# FPC_15ICS_80LEDS_150MM.net
KiCad netlist of a schematic drawn in Altium Designer
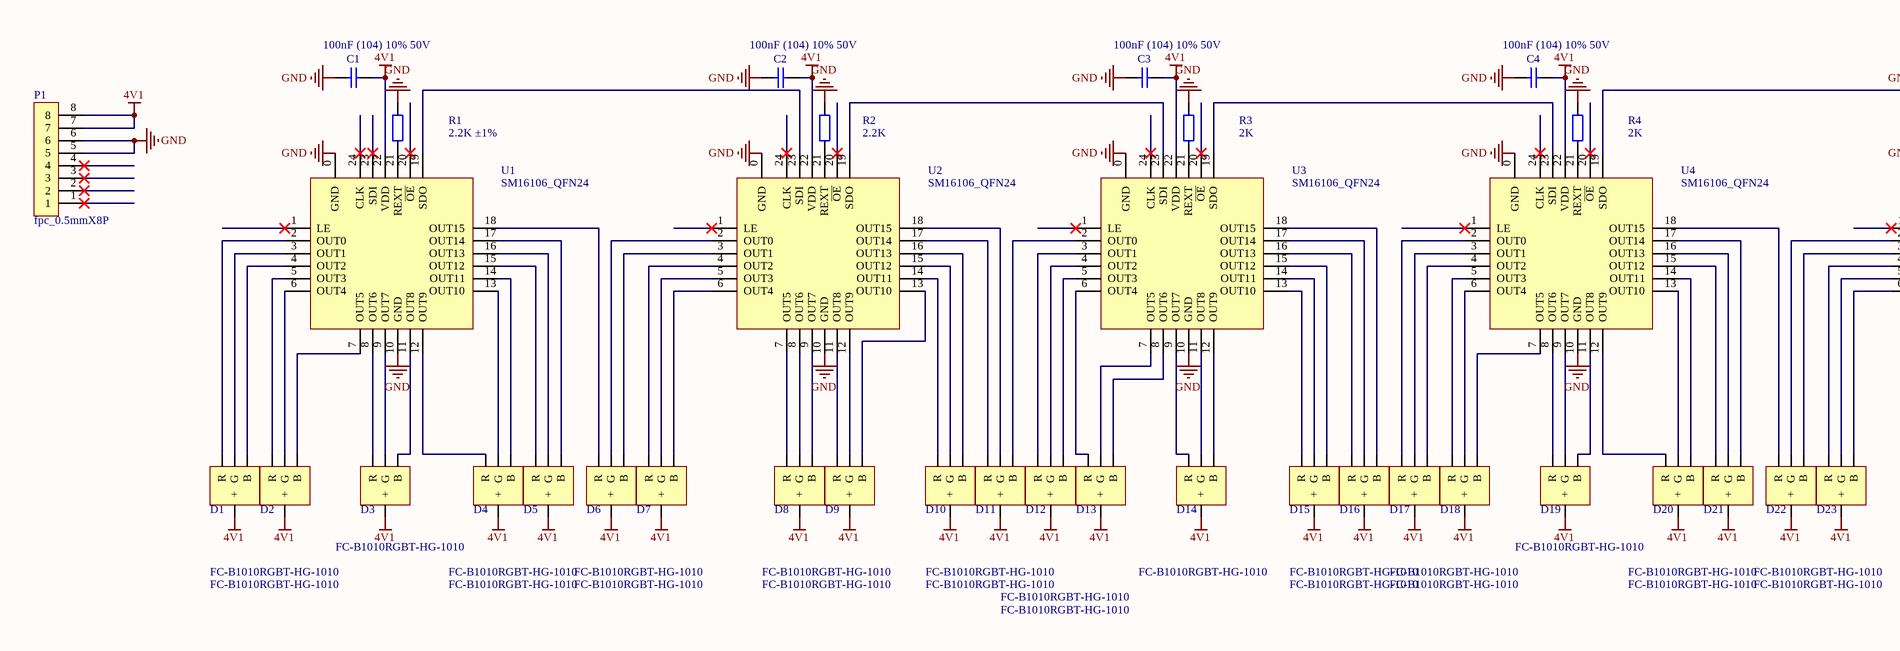
[diagram p0: FPC_15ICS_80LEDS_150MM.SchDoc, left]
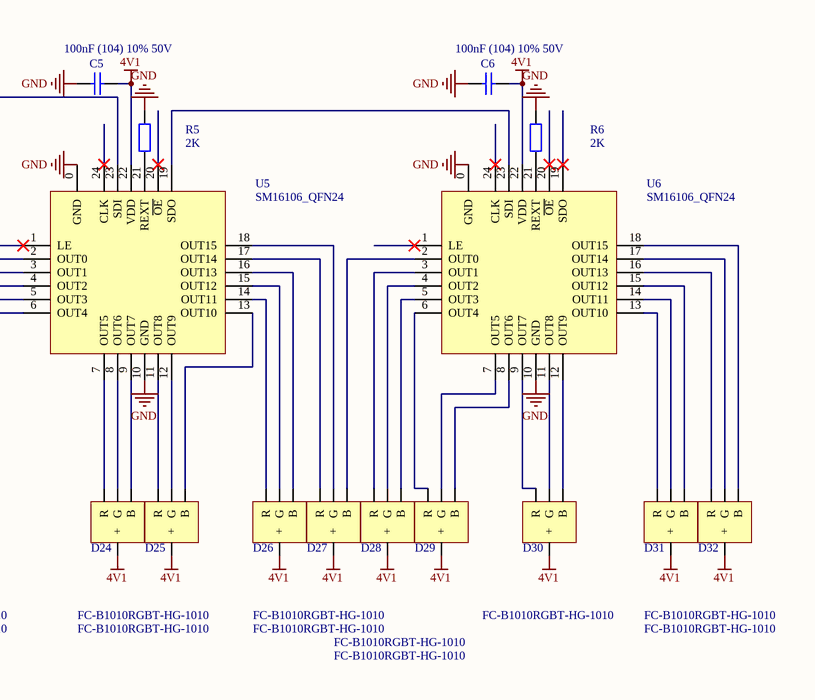
[diagram p1: FPC_15ICS_80LEDS_150MM.SchDoc, right]

(export (version "E")
  (design (tool "Eeschema 10.0.6"))
  (components
    (comp (ref "C1")
      (value "100nF (104) 10% 50V")
      (footprint "0402_C")
      (description "贴片电容")
      (libsource (lib "Cap") (part "0603 100nF (104) 10% 50V"))
    )
    (comp (ref "C2")
      (value "100nF (104) 10% 50V")
      (footprint "0402_C")
      (description "贴片电容")
      (libsource (lib "Cap") (part "0603 100nF (104) 10% 50V"))
    )
    (comp (ref "C3")
      (value "100nF (104) 10% 50V")
      (footprint "0402_C")
      (description "贴片电容")
      (libsource (lib "Cap") (part "0603 100nF (104) 10% 50V"))
    )
    (comp (ref "C4")
      (value "100nF (104) 10% 50V")
      (footprint "0402_C")
      (description "贴片电容")
      (libsource (lib "Cap") (part "0603 100nF (104) 10% 50V"))
    )
    (comp (ref "C5")
      (value "100nF (104) 10% 50V")
      (footprint "0402_C")
      (description "贴片电容")
      (libsource (lib "Cap") (part "0603 100nF (104) 10% 50V"))
    )
    (comp (ref "C6")
      (value "100nF (104) 10% 50V")
      (footprint "0402_C")
      (description "贴片电容")
      (libsource (lib "Cap") (part "0603 100nF (104) 10% 50V"))
    )
    (comp (ref "D1")
      (value "FC-B1010RGBT-HG-1010")
      (footprint "LED-SMD-0.385X0.45X0.45")
      (libsource (lib "TCPLib") (part "LED_RGB_1010"))
    )
    (comp (ref "D2")
      (value "FC-B1010RGBT-HG-1010")
      (footprint "LED-SMD-0.385X0.45X0.45")
      (libsource (lib "TCPLib") (part "LED_RGB_1010"))
    )
    (comp (ref "D3")
      (value "FC-B1010RGBT-HG-1010")
      (footprint "LED-SMD-0.385X0.45X0.45")
      (libsource (lib "TCPLib") (part "LED_RGB_1010"))
    )
    (comp (ref "D4")
      (value "FC-B1010RGBT-HG-1010")
      (footprint "LED-SMD-0.385X0.45X0.45")
      (libsource (lib "TCPLib") (part "LED_RGB_1010"))
    )
    (comp (ref "D5")
      (value "FC-B1010RGBT-HG-1010")
      (footprint "LED-SMD-0.385X0.45X0.45")
      (libsource (lib "TCPLib") (part "LED_RGB_1010"))
    )
    (comp (ref "D6")
      (value "FC-B1010RGBT-HG-1010")
      (footprint "LED-SMD-0.385X0.45X0.45")
      (libsource (lib "TCPLib") (part "LED_RGB_1010"))
    )
    (comp (ref "D7")
      (value "FC-B1010RGBT-HG-1010")
      (footprint "LED-SMD-0.385X0.45X0.45")
      (libsource (lib "TCPLib") (part "LED_RGB_1010"))
    )
    (comp (ref "D8")
      (value "FC-B1010RGBT-HG-1010")
      (footprint "LED-SMD-0.385X0.45X0.45")
      (libsource (lib "TCPLib") (part "LED_RGB_1010"))
    )
    (comp (ref "D9")
      (value "FC-B1010RGBT-HG-1010")
      (footprint "LED-SMD-0.385X0.45X0.45")
      (libsource (lib "TCPLib") (part "LED_RGB_1010"))
    )
    (comp (ref "D10")
      (value "FC-B1010RGBT-HG-1010")
      (footprint "LED-SMD-0.385X0.45X0.45")
      (libsource (lib "TCPLib") (part "LED_RGB_1010"))
    )
    (comp (ref "D11")
      (value "FC-B1010RGBT-HG-1010")
      (footprint "LED-SMD-0.385X0.45X0.45")
      (libsource (lib "TCPLib") (part "LED_RGB_1010"))
    )
    (comp (ref "D12")
      (value "FC-B1010RGBT-HG-1010")
      (footprint "LED-SMD-0.385X0.45X0.45")
      (libsource (lib "TCPLib") (part "LED_RGB_1010"))
    )
    (comp (ref "D13")
      (value "FC-B1010RGBT-HG-1010")
      (footprint "LED-SMD-0.385X0.45X0.45")
      (libsource (lib "TCPLib") (part "LED_RGB_1010"))
    )
    (comp (ref "D14")
      (value "FC-B1010RGBT-HG-1010")
      (footprint "LED-SMD-0.385X0.45X0.45")
      (libsource (lib "TCPLib") (part "LED_RGB_1010"))
    )
    (comp (ref "D15")
      (value "FC-B1010RGBT-HG-1010")
      (footprint "LED-SMD-0.385X0.45X0.45")
      (libsource (lib "TCPLib") (part "LED_RGB_1010"))
    )
    (comp (ref "D16")
      (value "FC-B1010RGBT-HG-1010")
      (footprint "LED-SMD-0.385X0.45X0.45")
      (libsource (lib "TCPLib") (part "LED_RGB_1010"))
    )
    (comp (ref "D17")
      (value "FC-B1010RGBT-HG-1010")
      (footprint "LED-SMD-0.385X0.45X0.45")
      (libsource (lib "TCPLib") (part "LED_RGB_1010"))
    )
    (comp (ref "D18")
      (value "FC-B1010RGBT-HG-1010")
      (footprint "LED-SMD-0.385X0.45X0.45")
      (libsource (lib "TCPLib") (part "LED_RGB_1010"))
    )
    (comp (ref "D19")
      (value "FC-B1010RGBT-HG-1010")
      (footprint "LED-SMD-0.385X0.45X0.45")
      (libsource (lib "TCPLib") (part "LED_RGB_1010"))
    )
    (comp (ref "D20")
      (value "FC-B1010RGBT-HG-1010")
      (footprint "LED-SMD-0.385X0.45X0.45")
      (libsource (lib "TCPLib") (part "LED_RGB_1010"))
    )
    (comp (ref "D21")
      (value "FC-B1010RGBT-HG-1010")
      (footprint "LED-SMD-0.385X0.45X0.45")
      (libsource (lib "TCPLib") (part "LED_RGB_1010"))
    )
    (comp (ref "D22")
      (value "FC-B1010RGBT-HG-1010")
      (footprint "LED-SMD-0.385X0.45X0.45")
      (libsource (lib "TCPLib") (part "LED_RGB_1010"))
    )
    (comp (ref "D23")
      (value "FC-B1010RGBT-HG-1010")
      (footprint "LED-SMD-0.385X0.45X0.45")
      (libsource (lib "TCPLib") (part "LED_RGB_1010"))
    )
    (comp (ref "D24")
      (value "FC-B1010RGBT-HG-1010")
      (footprint "LED-SMD-0.385X0.45X0.45")
      (libsource (lib "TCPLib") (part "LED_RGB_1010"))
    )
    (comp (ref "D25")
      (value "FC-B1010RGBT-HG-1010")
      (footprint "LED-SMD-0.385X0.45X0.45")
      (libsource (lib "TCPLib") (part "LED_RGB_1010"))
    )
    (comp (ref "D26")
      (value "FC-B1010RGBT-HG-1010")
      (footprint "LED-SMD-0.385X0.45X0.45")
      (libsource (lib "TCPLib") (part "LED_RGB_1010"))
    )
    (comp (ref "D27")
      (value "FC-B1010RGBT-HG-1010")
      (footprint "LED-SMD-0.385X0.45X0.45")
      (libsource (lib "TCPLib") (part "LED_RGB_1010"))
    )
    (comp (ref "D28")
      (value "FC-B1010RGBT-HG-1010")
      (footprint "LED-SMD-0.385X0.45X0.45")
      (libsource (lib "TCPLib") (part "LED_RGB_1010"))
    )
    (comp (ref "D29")
      (value "FC-B1010RGBT-HG-1010")
      (footprint "LED-SMD-0.385X0.45X0.45")
      (libsource (lib "TCPLib") (part "LED_RGB_1010"))
    )
    (comp (ref "D30")
      (value "FC-B1010RGBT-HG-1010")
      (footprint "LED-SMD-0.385X0.45X0.45")
      (libsource (lib "TCPLib") (part "LED_RGB_1010"))
    )
    (comp (ref "D31")
      (value "FC-B1010RGBT-HG-1010")
      (footprint "LED-SMD-0.385X0.45X0.45")
      (libsource (lib "TCPLib") (part "LED_RGB_1010"))
    )
    (comp (ref "D32")
      (value "FC-B1010RGBT-HG-1010")
      (footprint "LED-SMD-0.385X0.45X0.45")
      (libsource (lib "TCPLib") (part "LED_RGB_1010"))
    )
    (comp (ref "P1")
      (value "fpc_0.5mmX8P")
      (footprint "goldfiger_fpc_8")
      (libsource (lib "TCPLib") (part "fpc_0.5mmX8P"))
    )
    (comp (ref "R1")
      (value "2.2K ±1%")
      (footprint "0603_R")
      (description "贴片电阻")
      (libsource (lib "RES") (part "0603 6.2KΩ (6201) 1%"))
    )
    (comp (ref "R2")
      (value "2.2K")
      (footprint "0603_R")
      (description "贴片电阻")
      (libsource (lib "RES") (part "0603 4.7KΩ (4701) 1%"))
    )
    (comp (ref "R3")
      (value "2K")
      (footprint "0603_R")
      (description "贴片电阻")
      (libsource (lib "RES") (part "0603 3.6KΩ (3601) 1%"))
    )
    (comp (ref "R4")
      (value "2K")
      (footprint "0603_R")
      (description "贴片电阻")
      (libsource (lib "RES") (part "0603 6.2KΩ (6201) 1%"))
    )
    (comp (ref "R5")
      (value "2K")
      (footprint "0603_R")
      (description "贴片电阻")
      (libsource (lib "RES") (part "0603 4.7KΩ (4701) 1%"))
    )
    (comp (ref "R6")
      (value "2K")
      (footprint "0603_R")
      (description "贴片电阻")
      (libsource (lib "RES") (part "0603 3.6KΩ (3601) 1%"))
    )
    (comp (ref "U1")
      (value "SM16106_QFN24")
      (footprint "QFN-24_4x4x05tcp")
      (libsource (lib "TCPLib") (part "SM16106_QFN24"))
    )
    (comp (ref "U2")
      (value "SM16106_QFN24")
      (footprint "QFN-24_4x4x05tcp")
      (libsource (lib "TCPLib") (part "SM16106_QFN24"))
    )
    (comp (ref "U3")
      (value "SM16106_QFN24")
      (footprint "QFN-24_4x4x05tcp")
      (libsource (lib "TCPLib") (part "SM16106_QFN24"))
    )
    (comp (ref "U4")
      (value "SM16106_QFN24")
      (footprint "QFN-24_4x4x05tcp")
      (libsource (lib "TCPLib") (part "SM16106_QFN24"))
    )
    (comp (ref "U5")
      (value "SM16106_QFN24")
      (footprint "QFN-24_4x4x05tcp")
      (libsource (lib "TCPLib") (part "SM16106_QFN24"))
    )
    (comp (ref "U6")
      (value "SM16106_QFN24")
      (footprint "QFN-24_4x4x05tcp")
      (libsource (lib "TCPLib") (part "SM16106_QFN24"))
    )
  )
  (nets
    (net (code "1") (name "4V1") (class "Default")
      (node (ref "C1") (pin "2") (pinfunction "2_2") (pintype "passive"))
      (node (ref "C2") (pin "2") (pinfunction "2_2") (pintype "passive"))
      (node (ref "C3") (pin "2") (pinfunction "2_2") (pintype "passive"))
      (node (ref "C4") (pin "2") (pinfunction "2_2") (pintype "passive"))
      (node (ref "C5") (pin "2") (pinfunction "2_2") (pintype "passive"))
      (node (ref "C6") (pin "2") (pinfunction "2_2") (pintype "passive"))
      (node (ref "D1") (pin "1") (pinfunction "+_1") (pintype "passive"))
      (node (ref "D10") (pin "1") (pinfunction "+_1") (pintype "passive"))
      (node (ref "D11") (pin "1") (pinfunction "+_1") (pintype "passive"))
      (node (ref "D12") (pin "1") (pinfunction "+_1") (pintype "passive"))
      (node (ref "D13") (pin "1") (pinfunction "+_1") (pintype "passive"))
      (node (ref "D14") (pin "1") (pinfunction "+_1") (pintype "passive"))
      (node (ref "D15") (pin "1") (pinfunction "+_1") (pintype "passive"))
      (node (ref "D16") (pin "1") (pinfunction "+_1") (pintype "passive"))
      (node (ref "D17") (pin "1") (pinfunction "+_1") (pintype "passive"))
      (node (ref "D18") (pin "1") (pinfunction "+_1") (pintype "passive"))
      (node (ref "D19") (pin "1") (pinfunction "+_1") (pintype "passive"))
      (node (ref "D2") (pin "1") (pinfunction "+_1") (pintype "passive"))
      (node (ref "D20") (pin "1") (pinfunction "+_1") (pintype "passive"))
      (node (ref "D21") (pin "1") (pinfunction "+_1") (pintype "passive"))
      (node (ref "D22") (pin "1") (pinfunction "+_1") (pintype "passive"))
      (node (ref "D23") (pin "1") (pinfunction "+_1") (pintype "passive"))
      (node (ref "D24") (pin "1") (pinfunction "+_1") (pintype "passive"))
      (node (ref "D25") (pin "1") (pinfunction "+_1") (pintype "passive"))
      (node (ref "D26") (pin "1") (pinfunction "+_1") (pintype "passive"))
      (node (ref "D27") (pin "1") (pinfunction "+_1") (pintype "passive"))
      (node (ref "D28") (pin "1") (pinfunction "+_1") (pintype "passive"))
      (node (ref "D29") (pin "1") (pinfunction "+_1") (pintype "passive"))
      (node (ref "D3") (pin "1") (pinfunction "+_1") (pintype "passive"))
      (node (ref "D30") (pin "1") (pinfunction "+_1") (pintype "passive"))
      (node (ref "D31") (pin "1") (pinfunction "+_1") (pintype "passive"))
      (node (ref "D32") (pin "1") (pinfunction "+_1") (pintype "passive"))
      (node (ref "D4") (pin "1") (pinfunction "+_1") (pintype "passive"))
      (node (ref "D5") (pin "1") (pinfunction "+_1") (pintype "passive"))
      (node (ref "D6") (pin "1") (pinfunction "+_1") (pintype "passive"))
      (node (ref "D7") (pin "1") (pinfunction "+_1") (pintype "passive"))
      (node (ref "D8") (pin "1") (pinfunction "+_1") (pintype "passive"))
      (node (ref "D9") (pin "1") (pinfunction "+_1") (pintype "passive"))
      (node (ref "P1") (pin "7") (pinfunction "7_7") (pintype "passive"))
      (node (ref "P1") (pin "8") (pinfunction "8_8") (pintype "passive"))
      (node (ref "U1") (pin "22") (pinfunction "VDD_22") (pintype "passive"))
      (node (ref "U2") (pin "22") (pinfunction "VDD_22") (pintype "passive"))
      (node (ref "U3") (pin "22") (pinfunction "VDD_22") (pintype "passive"))
      (node (ref "U4") (pin "22") (pinfunction "VDD_22") (pintype "passive"))
      (node (ref "U5") (pin "22") (pinfunction "VDD_22") (pintype "passive"))
      (node (ref "U6") (pin "22") (pinfunction "VDD_22") (pintype "passive"))
    )
    (net (code "2") (name "GND") (class "Default")
      (node (ref "C1") (pin "1") (pinfunction "1_1") (pintype "passive"))
      (node (ref "C2") (pin "1") (pinfunction "1_1") (pintype "passive"))
      (node (ref "C3") (pin "1") (pinfunction "1_1") (pintype "passive"))
      (node (ref "C4") (pin "1") (pinfunction "1_1") (pintype "passive"))
      (node (ref "C5") (pin "1") (pinfunction "1_1") (pintype "passive"))
      (node (ref "C6") (pin "1") (pinfunction "1_1") (pintype "passive"))
      (node (ref "P1") (pin "5") (pinfunction "5_5") (pintype "passive"))
      (node (ref "P1") (pin "6") (pinfunction "6_6") (pintype "passive"))
      (node (ref "R1") (pin "2") (pinfunction "2_2") (pintype "passive"))
      (node (ref "R2") (pin "2") (pinfunction "2_2") (pintype "passive"))
      (node (ref "R3") (pin "2") (pinfunction "2_2") (pintype "passive"))
      (node (ref "R4") (pin "2") (pinfunction "2_2") (pintype "passive"))
      (node (ref "R5") (pin "2") (pinfunction "2_2") (pintype "passive"))
      (node (ref "R6") (pin "2") (pinfunction "2_2") (pintype "passive"))
      (node (ref "U1") (pin "0") (pinfunction "GND_0") (pintype "passive"))
      (node (ref "U1") (pin "10") (pinfunction "GND_10") (pintype "passive"))
      (node (ref "U2") (pin "0") (pinfunction "GND_0") (pintype "passive"))
      (node (ref "U2") (pin "10") (pinfunction "GND_10") (pintype "passive"))
      (node (ref "U3") (pin "0") (pinfunction "GND_0") (pintype "passive"))
      (node (ref "U3") (pin "10") (pinfunction "GND_10") (pintype "passive"))
      (node (ref "U4") (pin "0") (pinfunction "GND_0") (pintype "passive"))
      (node (ref "U4") (pin "10") (pinfunction "GND_10") (pintype "passive"))
      (node (ref "U5") (pin "0") (pinfunction "GND_0") (pintype "passive"))
      (node (ref "U5") (pin "10") (pinfunction "GND_10") (pintype "passive"))
      (node (ref "U6") (pin "0") (pinfunction "GND_0") (pintype "passive"))
      (node (ref "U6") (pin "10") (pinfunction "GND_10") (pintype "passive"))
    )
    (net (code "3") (name "Net-(D1-B)") (class "Default")
      (node (ref "D1") (pin "4") (pinfunction "B_4") (pintype "passive"))
      (node (ref "U1") (pin "4") (pinfunction "OUT2_4") (pintype "passive"))
    )
    (net (code "4") (name "Net-(D1-G)") (class "Default")
      (node (ref "D1") (pin "3") (pinfunction "G_3") (pintype "passive"))
      (node (ref "U1") (pin "3") (pinfunction "OUT1_3") (pintype "passive"))
    )
    (net (code "5") (name "Net-(D1-R)") (class "Default")
      (node (ref "D1") (pin "2") (pinfunction "R_2") (pintype "passive"))
      (node (ref "U1") (pin "2") (pinfunction "OUT0_2") (pintype "passive"))
    )
    (net (code "6") (name "Net-(D2-B)") (class "Default")
      (node (ref "D2") (pin "4") (pinfunction "B_4") (pintype "passive"))
      (node (ref "U1") (pin "7") (pinfunction "OUT5_7") (pintype "passive"))
    )
    (net (code "7") (name "Net-(D2-G)") (class "Default")
      (node (ref "D2") (pin "3") (pinfunction "G_3") (pintype "passive"))
      (node (ref "U1") (pin "6") (pinfunction "OUT4_6") (pintype "passive"))
    )
    (net (code "8") (name "Net-(D2-R)") (class "Default")
      (node (ref "D2") (pin "2") (pinfunction "R_2") (pintype "passive"))
      (node (ref "U1") (pin "5") (pinfunction "OUT3_5") (pintype "passive"))
    )
    (net (code "9") (name "Net-(D3-B)") (class "Default")
      (node (ref "D3") (pin "4") (pinfunction "B_4") (pintype "passive"))
      (node (ref "U1") (pin "11") (pinfunction "OUT8_11") (pintype "passive"))
    )
    (net (code "10") (name "Net-(D3-G)") (class "Default")
      (node (ref "D3") (pin "3") (pinfunction "G_3") (pintype "passive"))
      (node (ref "U1") (pin "9") (pinfunction "OUT7_9") (pintype "passive"))
    )
    (net (code "11") (name "Net-(D3-R)") (class "Default")
      (node (ref "D3") (pin "2") (pinfunction "R_2") (pintype "passive"))
      (node (ref "U1") (pin "8") (pinfunction "OUT6_8") (pintype "passive"))
    )
    (net (code "12") (name "Net-(D4-B)") (class "Default")
      (node (ref "D4") (pin "4") (pinfunction "B_4") (pintype "passive"))
      (node (ref "U1") (pin "14") (pinfunction "OUT11_14") (pintype "passive"))
    )
    (net (code "13") (name "Net-(D4-G)") (class "Default")
      (node (ref "D4") (pin "3") (pinfunction "G_3") (pintype "passive"))
      (node (ref "U1") (pin "13") (pinfunction "OUT10_13") (pintype "passive"))
    )
    (net (code "14") (name "Net-(D4-R)") (class "Default")
      (node (ref "D4") (pin "2") (pinfunction "R_2") (pintype "passive"))
      (node (ref "U1") (pin "12") (pinfunction "OUT9_12") (pintype "passive"))
    )
    (net (code "15") (name "Net-(D5-B)") (class "Default")
      (node (ref "D5") (pin "4") (pinfunction "B_4") (pintype "passive"))
      (node (ref "U1") (pin "17") (pinfunction "OUT14_17") (pintype "passive"))
    )
    (net (code "16") (name "Net-(D5-G)") (class "Default")
      (node (ref "D5") (pin "3") (pinfunction "G_3") (pintype "passive"))
      (node (ref "U1") (pin "16") (pinfunction "OUT13_16") (pintype "passive"))
    )
    (net (code "17") (name "Net-(D5-R)") (class "Default")
      (node (ref "D5") (pin "2") (pinfunction "R_2") (pintype "passive"))
      (node (ref "U1") (pin "15") (pinfunction "OUT12_15") (pintype "passive"))
    )
    (net (code "18") (name "Net-(D6-B)") (class "Default")
      (node (ref "D6") (pin "4") (pinfunction "B_4") (pintype "passive"))
      (node (ref "U2") (pin "3") (pinfunction "OUT1_3") (pintype "passive"))
    )
    (net (code "19") (name "Net-(D6-G)") (class "Default")
      (node (ref "D6") (pin "3") (pinfunction "G_3") (pintype "passive"))
      (node (ref "U2") (pin "2") (pinfunction "OUT0_2") (pintype "passive"))
    )
    (net (code "20") (name "Net-(D6-R)") (class "Default")
      (node (ref "D6") (pin "2") (pinfunction "R_2") (pintype "passive"))
      (node (ref "U1") (pin "18") (pinfunction "OUT15_18") (pintype "passive"))
    )
    (net (code "21") (name "Net-(D7-B)") (class "Default")
      (node (ref "D7") (pin "4") (pinfunction "B_4") (pintype "passive"))
      (node (ref "U2") (pin "6") (pinfunction "OUT4_6") (pintype "passive"))
    )
    (net (code "22") (name "Net-(D7-G)") (class "Default")
      (node (ref "D7") (pin "3") (pinfunction "G_3") (pintype "passive"))
      (node (ref "U2") (pin "5") (pinfunction "OUT3_5") (pintype "passive"))
    )
    (net (code "23") (name "Net-(D7-R)") (class "Default")
      (node (ref "D7") (pin "2") (pinfunction "R_2") (pintype "passive"))
      (node (ref "U2") (pin "4") (pinfunction "OUT2_4") (pintype "passive"))
    )
    (net (code "24") (name "Net-(D8-B)") (class "Default")
      (node (ref "D8") (pin "4") (pinfunction "B_4") (pintype "passive"))
      (node (ref "U2") (pin "9") (pinfunction "OUT7_9") (pintype "passive"))
    )
    (net (code "25") (name "Net-(D8-G)") (class "Default")
      (node (ref "D8") (pin "3") (pinfunction "G_3") (pintype "passive"))
      (node (ref "U2") (pin "8") (pinfunction "OUT6_8") (pintype "passive"))
    )
    (net (code "26") (name "Net-(D8-R)") (class "Default")
      (node (ref "D8") (pin "2") (pinfunction "R_2") (pintype "passive"))
      (node (ref "U2") (pin "7") (pinfunction "OUT5_7") (pintype "passive"))
    )
    (net (code "27") (name "Net-(D9-B)") (class "Default")
      (node (ref "D9") (pin "4") (pinfunction "B_4") (pintype "passive"))
      (node (ref "U2") (pin "13") (pinfunction "OUT10_13") (pintype "passive"))
    )
    (net (code "28") (name "Net-(D9-G)") (class "Default")
      (node (ref "D9") (pin "3") (pinfunction "G_3") (pintype "passive"))
      (node (ref "U2") (pin "12") (pinfunction "OUT9_12") (pintype "passive"))
    )
    (net (code "29") (name "Net-(D9-R)") (class "Default")
      (node (ref "D9") (pin "2") (pinfunction "R_2") (pintype "passive"))
      (node (ref "U2") (pin "11") (pinfunction "OUT8_11") (pintype "passive"))
    )
    (net (code "30") (name "Net-(D10-B)") (class "Default")
      (node (ref "D10") (pin "4") (pinfunction "B_4") (pintype "passive"))
      (node (ref "U2") (pin "16") (pinfunction "OUT13_16") (pintype "passive"))
    )
    (net (code "31") (name "Net-(D10-G)") (class "Default")
      (node (ref "D10") (pin "3") (pinfunction "G_3") (pintype "passive"))
      (node (ref "U2") (pin "15") (pinfunction "OUT12_15") (pintype "passive"))
    )
    (net (code "32") (name "Net-(D10-R)") (class "Default")
      (node (ref "D10") (pin "2") (pinfunction "R_2") (pintype "passive"))
      (node (ref "U2") (pin "14") (pinfunction "OUT11_14") (pintype "passive"))
    )
    (net (code "33") (name "Net-(D11-B)") (class "Default")
      (node (ref "D11") (pin "4") (pinfunction "B_4") (pintype "passive"))
      (node (ref "U3") (pin "2") (pinfunction "OUT0_2") (pintype "passive"))
    )
    (net (code "34") (name "Net-(D11-G)") (class "Default")
      (node (ref "D11") (pin "3") (pinfunction "G_3") (pintype "passive"))
      (node (ref "U2") (pin "18") (pinfunction "OUT15_18") (pintype "passive"))
    )
    (net (code "35") (name "Net-(D11-R)") (class "Default")
      (node (ref "D11") (pin "2") (pinfunction "R_2") (pintype "passive"))
      (node (ref "U2") (pin "17") (pinfunction "OUT14_17") (pintype "passive"))
    )
    (net (code "36") (name "Net-(D12-B)") (class "Default")
      (node (ref "D12") (pin "4") (pinfunction "B_4") (pintype "passive"))
      (node (ref "U3") (pin "5") (pinfunction "OUT3_5") (pintype "passive"))
    )
    (net (code "37") (name "Net-(D12-G)") (class "Default")
      (node (ref "D12") (pin "3") (pinfunction "G_3") (pintype "passive"))
      (node (ref "U3") (pin "4") (pinfunction "OUT2_4") (pintype "passive"))
    )
    (net (code "38") (name "Net-(D12-R)") (class "Default")
      (node (ref "D12") (pin "2") (pinfunction "R_2") (pintype "passive"))
      (node (ref "U3") (pin "3") (pinfunction "OUT1_3") (pintype "passive"))
    )
    (net (code "39") (name "Net-(D13-B)") (class "Default")
      (node (ref "D13") (pin "4") (pinfunction "B_4") (pintype "passive"))
      (node (ref "U3") (pin "8") (pinfunction "OUT6_8") (pintype "passive"))
    )
    (net (code "40") (name "Net-(D13-G)") (class "Default")
      (node (ref "D13") (pin "3") (pinfunction "G_3") (pintype "passive"))
      (node (ref "U3") (pin "7") (pinfunction "OUT5_7") (pintype "passive"))
    )
    (net (code "41") (name "Net-(D13-R)") (class "Default")
      (node (ref "D13") (pin "2") (pinfunction "R_2") (pintype "passive"))
      (node (ref "U3") (pin "6") (pinfunction "OUT4_6") (pintype "passive"))
    )
    (net (code "42") (name "Net-(D14-B)") (class "Default")
      (node (ref "D14") (pin "4") (pinfunction "B_4") (pintype "passive"))
      (node (ref "U3") (pin "12") (pinfunction "OUT9_12") (pintype "passive"))
    )
    (net (code "43") (name "Net-(D14-G)") (class "Default")
      (node (ref "D14") (pin "3") (pinfunction "G_3") (pintype "passive"))
      (node (ref "U3") (pin "11") (pinfunction "OUT8_11") (pintype "passive"))
    )
    (net (code "44") (name "Net-(D14-R)") (class "Default")
      (node (ref "D14") (pin "2") (pinfunction "R_2") (pintype "passive"))
      (node (ref "U3") (pin "9") (pinfunction "OUT7_9") (pintype "passive"))
    )
    (net (code "45") (name "Net-(D15-B)") (class "Default")
      (node (ref "D15") (pin "4") (pinfunction "B_4") (pintype "passive"))
      (node (ref "U3") (pin "15") (pinfunction "OUT12_15") (pintype "passive"))
    )
    (net (code "46") (name "Net-(D15-G)") (class "Default")
      (node (ref "D15") (pin "3") (pinfunction "G_3") (pintype "passive"))
      (node (ref "U3") (pin "14") (pinfunction "OUT11_14") (pintype "passive"))
    )
    (net (code "47") (name "Net-(D15-R)") (class "Default")
      (node (ref "D15") (pin "2") (pinfunction "R_2") (pintype "passive"))
      (node (ref "U3") (pin "13") (pinfunction "OUT10_13") (pintype "passive"))
    )
    (net (code "48") (name "Net-(D16-B)") (class "Default")
      (node (ref "D16") (pin "4") (pinfunction "B_4") (pintype "passive"))
      (node (ref "U3") (pin "18") (pinfunction "OUT15_18") (pintype "passive"))
    )
    (net (code "49") (name "Net-(D16-G)") (class "Default")
      (node (ref "D16") (pin "3") (pinfunction "G_3") (pintype "passive"))
      (node (ref "U3") (pin "17") (pinfunction "OUT14_17") (pintype "passive"))
    )
    (net (code "50") (name "Net-(D16-R)") (class "Default")
      (node (ref "D16") (pin "2") (pinfunction "R_2") (pintype "passive"))
      (node (ref "U3") (pin "16") (pinfunction "OUT13_16") (pintype "passive"))
    )
    (net (code "51") (name "Net-(D17-B)") (class "Default")
      (node (ref "D17") (pin "4") (pinfunction "B_4") (pintype "passive"))
      (node (ref "U4") (pin "4") (pinfunction "OUT2_4") (pintype "passive"))
    )
    (net (code "52") (name "Net-(D17-G)") (class "Default")
      (node (ref "D17") (pin "3") (pinfunction "G_3") (pintype "passive"))
      (node (ref "U4") (pin "3") (pinfunction "OUT1_3") (pintype "passive"))
    )
    (net (code "53") (name "Net-(D17-R)") (class "Default")
      (node (ref "D17") (pin "2") (pinfunction "R_2") (pintype "passive"))
      (node (ref "U4") (pin "2") (pinfunction "OUT0_2") (pintype "passive"))
    )
    (net (code "54") (name "Net-(D18-B)") (class "Default")
      (node (ref "D18") (pin "4") (pinfunction "B_4") (pintype "passive"))
      (node (ref "U4") (pin "7") (pinfunction "OUT5_7") (pintype "passive"))
    )
    (net (code "55") (name "Net-(D18-G)") (class "Default")
      (node (ref "D18") (pin "3") (pinfunction "G_3") (pintype "passive"))
      (node (ref "U4") (pin "6") (pinfunction "OUT4_6") (pintype "passive"))
    )
    (net (code "56") (name "Net-(D18-R)") (class "Default")
      (node (ref "D18") (pin "2") (pinfunction "R_2") (pintype "passive"))
      (node (ref "U4") (pin "5") (pinfunction "OUT3_5") (pintype "passive"))
    )
    (net (code "57") (name "Net-(D19-B)") (class "Default")
      (node (ref "D19") (pin "4") (pinfunction "B_4") (pintype "passive"))
      (node (ref "U4") (pin "11") (pinfunction "OUT8_11") (pintype "passive"))
    )
    (net (code "58") (name "Net-(D19-G)") (class "Default")
      (node (ref "D19") (pin "3") (pinfunction "G_3") (pintype "passive"))
      (node (ref "U4") (pin "9") (pinfunction "OUT7_9") (pintype "passive"))
    )
    (net (code "59") (name "Net-(D19-R)") (class "Default")
      (node (ref "D19") (pin "2") (pinfunction "R_2") (pintype "passive"))
      (node (ref "U4") (pin "8") (pinfunction "OUT6_8") (pintype "passive"))
    )
    (net (code "60") (name "Net-(D20-B)") (class "Default")
      (node (ref "D20") (pin "4") (pinfunction "B_4") (pintype "passive"))
      (node (ref "U4") (pin "14") (pinfunction "OUT11_14") (pintype "passive"))
    )
    (net (code "61") (name "Net-(D20-G)") (class "Default")
      (node (ref "D20") (pin "3") (pinfunction "G_3") (pintype "passive"))
      (node (ref "U4") (pin "13") (pinfunction "OUT10_13") (pintype "passive"))
    )
    (net (code "62") (name "Net-(D20-R)") (class "Default")
      (node (ref "D20") (pin "2") (pinfunction "R_2") (pintype "passive"))
      (node (ref "U4") (pin "12") (pinfunction "OUT9_12") (pintype "passive"))
    )
    (net (code "63") (name "Net-(D21-B)") (class "Default")
      (node (ref "D21") (pin "4") (pinfunction "B_4") (pintype "passive"))
      (node (ref "U4") (pin "17") (pinfunction "OUT14_17") (pintype "passive"))
    )
    (net (code "64") (name "Net-(D21-G)") (class "Default")
      (node (ref "D21") (pin "3") (pinfunction "G_3") (pintype "passive"))
      (node (ref "U4") (pin "16") (pinfunction "OUT13_16") (pintype "passive"))
    )
    (net (code "65") (name "Net-(D21-R)") (class "Default")
      (node (ref "D21") (pin "2") (pinfunction "R_2") (pintype "passive"))
      (node (ref "U4") (pin "15") (pinfunction "OUT12_15") (pintype "passive"))
    )
    (net (code "66") (name "Net-(D22-B)") (class "Default")
      (node (ref "D22") (pin "4") (pinfunction "B_4") (pintype "passive"))
      (node (ref "U5") (pin "3") (pinfunction "OUT1_3") (pintype "passive"))
    )
    (net (code "67") (name "Net-(D22-G)") (class "Default")
      (node (ref "D22") (pin "3") (pinfunction "G_3") (pintype "passive"))
      (node (ref "U5") (pin "2") (pinfunction "OUT0_2") (pintype "passive"))
    )
    (net (code "68") (name "Net-(D22-R)") (class "Default")
      (node (ref "D22") (pin "2") (pinfunction "R_2") (pintype "passive"))
      (node (ref "U4") (pin "18") (pinfunction "OUT15_18") (pintype "passive"))
    )
    (net (code "69") (name "Net-(D23-B)") (class "Default")
      (node (ref "D23") (pin "4") (pinfunction "B_4") (pintype "passive"))
      (node (ref "U5") (pin "6") (pinfunction "OUT4_6") (pintype "passive"))
    )
    (net (code "70") (name "Net-(D23-G)") (class "Default")
      (node (ref "D23") (pin "3") (pinfunction "G_3") (pintype "passive"))
      (node (ref "U5") (pin "5") (pinfunction "OUT3_5") (pintype "passive"))
    )
    (net (code "71") (name "Net-(D23-R)") (class "Default")
      (node (ref "D23") (pin "2") (pinfunction "R_2") (pintype "passive"))
      (node (ref "U5") (pin "4") (pinfunction "OUT2_4") (pintype "passive"))
    )
    (net (code "72") (name "Net-(D24-B)") (class "Default")
      (node (ref "D24") (pin "4") (pinfunction "B_4") (pintype "passive"))
      (node (ref "U5") (pin "9") (pinfunction "OUT7_9") (pintype "passive"))
    )
    (net (code "73") (name "Net-(D24-G)") (class "Default")
      (node (ref "D24") (pin "3") (pinfunction "G_3") (pintype "passive"))
      (node (ref "U5") (pin "8") (pinfunction "OUT6_8") (pintype "passive"))
    )
    (net (code "74") (name "Net-(D24-R)") (class "Default")
      (node (ref "D24") (pin "2") (pinfunction "R_2") (pintype "passive"))
      (node (ref "U5") (pin "7") (pinfunction "OUT5_7") (pintype "passive"))
    )
    (net (code "75") (name "Net-(D25-B)") (class "Default")
      (node (ref "D25") (pin "4") (pinfunction "B_4") (pintype "passive"))
      (node (ref "U5") (pin "13") (pinfunction "OUT10_13") (pintype "passive"))
    )
    (net (code "76") (name "Net-(D25-G)") (class "Default")
      (node (ref "D25") (pin "3") (pinfunction "G_3") (pintype "passive"))
      (node (ref "U5") (pin "12") (pinfunction "OUT9_12") (pintype "passive"))
    )
    (net (code "77") (name "Net-(D25-R)") (class "Default")
      (node (ref "D25") (pin "2") (pinfunction "R_2") (pintype "passive"))
      (node (ref "U5") (pin "11") (pinfunction "OUT8_11") (pintype "passive"))
    )
    (net (code "78") (name "Net-(D26-B)") (class "Default")
      (node (ref "D26") (pin "4") (pinfunction "B_4") (pintype "passive"))
      (node (ref "U5") (pin "16") (pinfunction "OUT13_16") (pintype "passive"))
    )
    (net (code "79") (name "Net-(D26-G)") (class "Default")
      (node (ref "D26") (pin "3") (pinfunction "G_3") (pintype "passive"))
      (node (ref "U5") (pin "15") (pinfunction "OUT12_15") (pintype "passive"))
    )
    (net (code "80") (name "Net-(D26-R)") (class "Default")
      (node (ref "D26") (pin "2") (pinfunction "R_2") (pintype "passive"))
      (node (ref "U5") (pin "14") (pinfunction "OUT11_14") (pintype "passive"))
    )
    (net (code "81") (name "Net-(D27-B)") (class "Default")
      (node (ref "D27") (pin "4") (pinfunction "B_4") (pintype "passive"))
      (node (ref "U6") (pin "2") (pinfunction "OUT0_2") (pintype "passive"))
    )
    (net (code "82") (name "Net-(D27-G)") (class "Default")
      (node (ref "D27") (pin "3") (pinfunction "G_3") (pintype "passive"))
      (node (ref "U5") (pin "18") (pinfunction "OUT15_18") (pintype "passive"))
    )
    (net (code "83") (name "Net-(D27-R)") (class "Default")
      (node (ref "D27") (pin "2") (pinfunction "R_2") (pintype "passive"))
      (node (ref "U5") (pin "17") (pinfunction "OUT14_17") (pintype "passive"))
    )
    (net (code "84") (name "Net-(D28-B)") (class "Default")
      (node (ref "D28") (pin "4") (pinfunction "B_4") (pintype "passive"))
      (node (ref "U6") (pin "5") (pinfunction "OUT3_5") (pintype "passive"))
    )
    (net (code "85") (name "Net-(D28-G)") (class "Default")
      (node (ref "D28") (pin "3") (pinfunction "G_3") (pintype "passive"))
      (node (ref "U6") (pin "4") (pinfunction "OUT2_4") (pintype "passive"))
    )
    (net (code "86") (name "Net-(D28-R)") (class "Default")
      (node (ref "D28") (pin "2") (pinfunction "R_2") (pintype "passive"))
      (node (ref "U6") (pin "3") (pinfunction "OUT1_3") (pintype "passive"))
    )
    (net (code "87") (name "Net-(D29-B)") (class "Default")
      (node (ref "D29") (pin "4") (pinfunction "B_4") (pintype "passive"))
      (node (ref "U6") (pin "8") (pinfunction "OUT6_8") (pintype "passive"))
    )
    (net (code "88") (name "Net-(D29-G)") (class "Default")
      (node (ref "D29") (pin "3") (pinfunction "G_3") (pintype "passive"))
      (node (ref "U6") (pin "7") (pinfunction "OUT5_7") (pintype "passive"))
    )
    (net (code "89") (name "Net-(D29-R)") (class "Default")
      (node (ref "D29") (pin "2") (pinfunction "R_2") (pintype "passive"))
      (node (ref "U6") (pin "6") (pinfunction "OUT4_6") (pintype "passive"))
    )
    (net (code "90") (name "Net-(D30-B)") (class "Default")
      (node (ref "D30") (pin "4") (pinfunction "B_4") (pintype "passive"))
      (node (ref "U6") (pin "12") (pinfunction "OUT9_12") (pintype "passive"))
    )
    (net (code "91") (name "Net-(D30-G)") (class "Default")
      (node (ref "D30") (pin "3") (pinfunction "G_3") (pintype "passive"))
      (node (ref "U6") (pin "11") (pinfunction "OUT8_11") (pintype "passive"))
    )
    (net (code "92") (name "Net-(D30-R)") (class "Default")
      (node (ref "D30") (pin "2") (pinfunction "R_2") (pintype "passive"))
      (node (ref "U6") (pin "9") (pinfunction "OUT7_9") (pintype "passive"))
    )
    (net (code "93") (name "Net-(D31-B)") (class "Default")
      (node (ref "D31") (pin "4") (pinfunction "B_4") (pintype "passive"))
      (node (ref "U6") (pin "15") (pinfunction "OUT12_15") (pintype "passive"))
    )
    (net (code "94") (name "Net-(D31-G)") (class "Default")
      (node (ref "D31") (pin "3") (pinfunction "G_3") (pintype "passive"))
      (node (ref "U6") (pin "14") (pinfunction "OUT11_14") (pintype "passive"))
    )
    (net (code "95") (name "Net-(D31-R)") (class "Default")
      (node (ref "D31") (pin "2") (pinfunction "R_2") (pintype "passive"))
      (node (ref "U6") (pin "13") (pinfunction "OUT10_13") (pintype "passive"))
    )
    (net (code "96") (name "Net-(D32-B)") (class "Default")
      (node (ref "D32") (pin "4") (pinfunction "B_4") (pintype "passive"))
      (node (ref "U6") (pin "18") (pinfunction "OUT15_18") (pintype "passive"))
    )
    (net (code "97") (name "Net-(D32-G)") (class "Default")
      (node (ref "D32") (pin "3") (pinfunction "G_3") (pintype "passive"))
      (node (ref "U6") (pin "17") (pinfunction "OUT14_17") (pintype "passive"))
    )
    (net (code "98") (name "Net-(D32-R)") (class "Default")
      (node (ref "D32") (pin "2") (pinfunction "R_2") (pintype "passive"))
      (node (ref "U6") (pin "16") (pinfunction "OUT13_16") (pintype "passive"))
    )
    (net (code "99") (name "Net-(U1-REXT)") (class "Default")
      (node (ref "R1") (pin "1") (pinfunction "1_1") (pintype "passive"))
      (node (ref "U1") (pin "21") (pinfunction "REXT_21") (pintype "passive"))
    )
    (net (code "100") (name "Net-(U1-SDO)") (class "Default")
      (node (ref "U1") (pin "19") (pinfunction "SDO_19") (pintype "passive"))
      (node (ref "U2") (pin "23") (pinfunction "SDI_23") (pintype "passive"))
    )
    (net (code "101") (name "Net-(U2-REXT)") (class "Default")
      (node (ref "R2") (pin "1") (pinfunction "1_1") (pintype "passive"))
      (node (ref "U2") (pin "21") (pinfunction "REXT_21") (pintype "passive"))
    )
    (net (code "102") (name "Net-(U2-SDO)") (class "Default")
      (node (ref "U2") (pin "19") (pinfunction "SDO_19") (pintype "passive"))
      (node (ref "U3") (pin "23") (pinfunction "SDI_23") (pintype "passive"))
    )
    (net (code "103") (name "Net-(U3-REXT)") (class "Default")
      (node (ref "R3") (pin "1") (pinfunction "1_1") (pintype "passive"))
      (node (ref "U3") (pin "21") (pinfunction "REXT_21") (pintype "passive"))
    )
    (net (code "104") (name "Net-(U3-SDO)") (class "Default")
      (node (ref "U3") (pin "19") (pinfunction "SDO_19") (pintype "passive"))
      (node (ref "U4") (pin "23") (pinfunction "SDI_23") (pintype "passive"))
    )
    (net (code "105") (name "Net-(U4-REXT)") (class "Default")
      (node (ref "R4") (pin "1") (pinfunction "1_1") (pintype "passive"))
      (node (ref "U4") (pin "21") (pinfunction "REXT_21") (pintype "passive"))
    )
    (net (code "106") (name "Net-(U4-SDO)") (class "Default")
      (node (ref "U4") (pin "19") (pinfunction "SDO_19") (pintype "passive"))
      (node (ref "U5") (pin "23") (pinfunction "SDI_23") (pintype "passive"))
    )
    (net (code "107") (name "Net-(U5-REXT)") (class "Default")
      (node (ref "R5") (pin "1") (pinfunction "1_1") (pintype "passive"))
      (node (ref "U5") (pin "21") (pinfunction "REXT_21") (pintype "passive"))
    )
    (net (code "108") (name "Net-(U5-SDO)") (class "Default")
      (node (ref "U5") (pin "19") (pinfunction "SDO_19") (pintype "passive"))
      (node (ref "U6") (pin "23") (pinfunction "SDI_23") (pintype "passive"))
    )
    (net (code "109") (name "Net-(U6-REXT)") (class "Default")
      (node (ref "R6") (pin "1") (pinfunction "1_1") (pintype "passive"))
      (node (ref "U6") (pin "21") (pinfunction "REXT_21") (pintype "passive"))
    )
    (net (code "110") (name "unconnected-(P1-Pad1)") (class "Default")
      (node (ref "P1") (pin "1") (pinfunction "1_1") (pintype "passive+no_connect"))
    )
    (net (code "111") (name "unconnected-(P1-Pad2)") (class "Default")
      (node (ref "P1") (pin "2") (pinfunction "2_2") (pintype "passive+no_connect"))
    )
    (net (code "112") (name "unconnected-(P1-Pad3)") (class "Default")
      (node (ref "P1") (pin "3") (pinfunction "3_3") (pintype "passive+no_connect"))
    )
    (net (code "113") (name "unconnected-(P1-Pad4)") (class "Default")
      (node (ref "P1") (pin "4") (pinfunction "4_4") (pintype "passive+no_connect"))
    )
    (net (code "114") (name "unconnected-(U1-CLK-Pad24)") (class "Default")
      (node (ref "U1") (pin "24") (pinfunction "CLK_24") (pintype "passive+no_connect"))
    )
    (net (code "115") (name "unconnected-(U1-LE-Pad1)") (class "Default")
      (node (ref "U1") (pin "1") (pinfunction "LE_1") (pintype "passive+no_connect"))
    )
    (net (code "116") (name "unconnected-(U1-SDI-Pad23)") (class "Default")
      (node (ref "U1") (pin "23") (pinfunction "SDI_23") (pintype "passive+no_connect"))
    )
    (net (code "117") (name "unconnected-(U1-~{OE}-Pad20)") (class "Default")
      (node (ref "U1") (pin "20") (pinfunction "~{OE}_20") (pintype "passive+no_connect"))
    )
    (net (code "118") (name "unconnected-(U2-CLK-Pad24)") (class "Default")
      (node (ref "U2") (pin "24") (pinfunction "CLK_24") (pintype "passive+no_connect"))
    )
    (net (code "119") (name "unconnected-(U2-LE-Pad1)") (class "Default")
      (node (ref "U2") (pin "1") (pinfunction "LE_1") (pintype "passive+no_connect"))
    )
    (net (code "120") (name "unconnected-(U2-~{OE}-Pad20)") (class "Default")
      (node (ref "U2") (pin "20") (pinfunction "~{OE}_20") (pintype "passive+no_connect"))
    )
    (net (code "121") (name "unconnected-(U3-CLK-Pad24)") (class "Default")
      (node (ref "U3") (pin "24") (pinfunction "CLK_24") (pintype "passive+no_connect"))
    )
    (net (code "122") (name "unconnected-(U3-LE-Pad1)") (class "Default")
      (node (ref "U3") (pin "1") (pinfunction "LE_1") (pintype "passive+no_connect"))
    )
    (net (code "123") (name "unconnected-(U3-~{OE}-Pad20)") (class "Default")
      (node (ref "U3") (pin "20") (pinfunction "~{OE}_20") (pintype "passive+no_connect"))
    )
    (net (code "124") (name "unconnected-(U4-CLK-Pad24)") (class "Default")
      (node (ref "U4") (pin "24") (pinfunction "CLK_24") (pintype "passive+no_connect"))
    )
    (net (code "125") (name "unconnected-(U4-LE-Pad1)") (class "Default")
      (node (ref "U4") (pin "1") (pinfunction "LE_1") (pintype "passive+no_connect"))
    )
    (net (code "126") (name "unconnected-(U4-~{OE}-Pad20)") (class "Default")
      (node (ref "U4") (pin "20") (pinfunction "~{OE}_20") (pintype "passive+no_connect"))
    )
    (net (code "127") (name "unconnected-(U5-CLK-Pad24)") (class "Default")
      (node (ref "U5") (pin "24") (pinfunction "CLK_24") (pintype "passive+no_connect"))
    )
    (net (code "128") (name "unconnected-(U5-LE-Pad1)") (class "Default")
      (node (ref "U5") (pin "1") (pinfunction "LE_1") (pintype "passive+no_connect"))
    )
    (net (code "129") (name "unconnected-(U5-~{OE}-Pad20)") (class "Default")
      (node (ref "U5") (pin "20") (pinfunction "~{OE}_20") (pintype "passive+no_connect"))
    )
    (net (code "130") (name "unconnected-(U6-CLK-Pad24)") (class "Default")
      (node (ref "U6") (pin "24") (pinfunction "CLK_24") (pintype "passive+no_connect"))
    )
    (net (code "131") (name "unconnected-(U6-LE-Pad1)") (class "Default")
      (node (ref "U6") (pin "1") (pinfunction "LE_1") (pintype "passive+no_connect"))
    )
    (net (code "132") (name "unconnected-(U6-SDO-Pad19)") (class "Default")
      (node (ref "U6") (pin "19") (pinfunction "SDO_19") (pintype "passive+no_connect"))
    )
    (net (code "133") (name "unconnected-(U6-~{OE}-Pad20)") (class "Default")
      (node (ref "U6") (pin "20") (pinfunction "~{OE}_20") (pintype "passive+no_connect"))
    )
  )
)
